# MiniD1_Schema.net
KiCad netlist of a schematic drawn in EAGLE
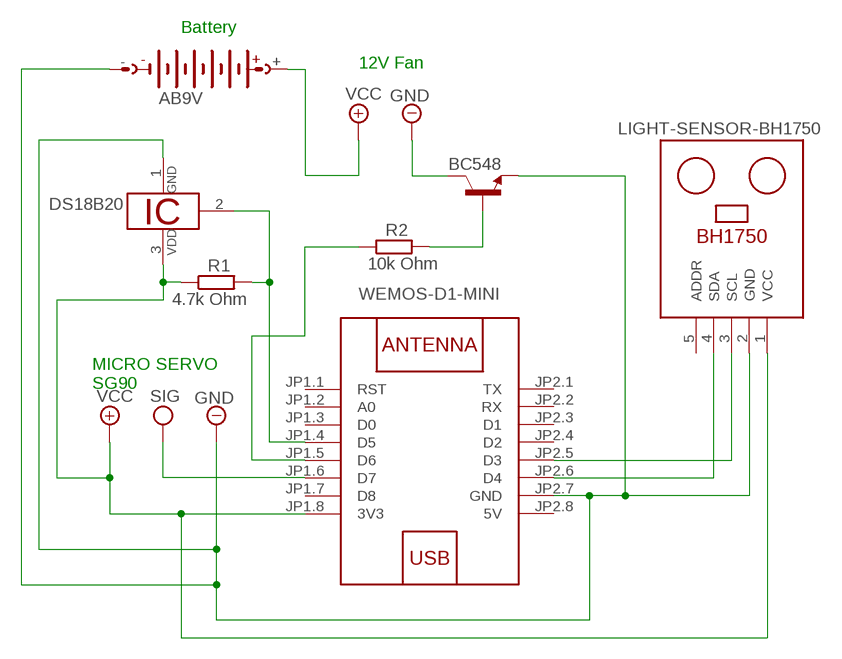
[diagram p0: schematic, sheet 1]

(export (version "E")
  (design (tool "Eeschema 10.0.6"))
  (components
    (comp (ref "G1")
      (value "AB9V")
      (footprint "eagle-import:AB9V")
      (libsource (lib "eagle-import") (part "AB9V"))
    )
    (comp (ref "IC1")
      (value "DS18B20")
      (footprint "eagle-import:TO92-")
      (libsource (lib "eagle-import") (part "DS18B20"))
    )
    (comp (ref "Q1")
      (value "BC548")
      (footprint "eagle-import:TO92-EBC")
      (libsource (lib "eagle-import") (part "BC548"))
    )
    (comp (ref "R1")
      (value "4.7k Ohm")
      (footprint "eagle-import:0207_10")
      (libsource (lib "eagle-import") (part "R-EU_0207/10"))
    )
    (comp (ref "R2")
      (value "10k Ohm")
      (footprint "eagle-import:0207_10")
      (libsource (lib "eagle-import") (part "R-EU_0207/10"))
    )
    (comp (ref "U$1")
      (value "WEMOS-D1-MINI")
      (footprint "eagle-import:WEMOS-D1-MINI")
      (libsource (lib "eagle-import") (part "WEMOS-D1-MINI"))
    )
    (comp (ref "U$2")
      (value "LIGHT-SENSOR-BH1750")
      (footprint "eagle-import:LIGHT-SENSOR-BH1750")
      (libsource (lib "eagle-import") (part "LIGHT-SENSOR-BH1750"))
    )
  )
  (nets
    (net (code "1") (name "/5V") (class "Default")
      (node (ref "U$1") (pin "JP2.8") (pinfunction "5V_JP2.8") (pintype "power_in"))
    )
    (net (code "2") (name "GND") (class "Default")
      (node (ref "G1") (pin "-") (pinfunction "-_-") (pintype "passive"))
      (node (ref "IC1") (pin "1") (pinfunction "GND_1") (pintype "power_in"))
      (node (ref "Q1") (pin "C") (pinfunction "C_C") (pintype "passive"))
      (node (ref "Q1") (pin "E") (pinfunction "E_E") (pintype "passive"))
      (node (ref "U$1") (pin "JP2.7") (pinfunction "GND_JP2.7") (pintype "power_in"))
      (node (ref "U$2") (pin "2") (pinfunction "GND_2") (pintype "power_in"))
    )
    (net (code "3") (name "Net-(IC1C-1W)") (class "Default")
      (node (ref "IC1") (pin "2") (pinfunction "1W_2") (pintype "power_in"))
      (node (ref "R1") (pin "2") (pinfunction "2_2") (pintype "passive"))
      (node (ref "U$1") (pin "JP1.4") (pinfunction "D5_JP1.4") (pintype "bidirectional"))
    )
    (net (code "4") (name "Net-(Q1-PadB)") (class "Default")
      (node (ref "Q1") (pin "B") (pinfunction "B_B") (pintype "passive"))
      (node (ref "R2") (pin "2") (pinfunction "2_2") (pintype "passive"))
    )
    (net (code "5") (name "Net-(U$1-D3)") (class "Default")
      (node (ref "U$1") (pin "JP2.5") (pinfunction "D3_JP2.5") (pintype "bidirectional"))
      (node (ref "U$2") (pin "3") (pinfunction "SCL_3") (pintype "bidirectional"))
    )
    (net (code "6") (name "Net-(U$1-D4)") (class "Default")
      (node (ref "U$1") (pin "JP2.6") (pinfunction "D4_JP2.6") (pintype "bidirectional"))
      (node (ref "U$2") (pin "4") (pinfunction "SDA_4") (pintype "bidirectional"))
    )
    (net (code "7") (name "Net-(U$1-D6)") (class "Default")
      (node (ref "R2") (pin "1") (pinfunction "1_1") (pintype "passive"))
      (node (ref "U$1") (pin "JP1.5") (pinfunction "D6_JP1.5") (pintype "bidirectional"))
    )
    (net (code "8") (name "SIG") (class "Default")
      (node (ref "U$1") (pin "JP1.6") (pinfunction "D7_JP1.6") (pintype "bidirectional"))
    )
    (net (code "9") (name "VCC") (class "Default")
      (node (ref "G1") (pin "+") (pinfunction "+_+") (pintype "passive"))
      (node (ref "IC1") (pin "3") (pinfunction "VDD_3") (pintype "power_in"))
      (node (ref "R1") (pin "1") (pinfunction "1_1") (pintype "passive"))
      (node (ref "U$1") (pin "JP1.8") (pinfunction "3V3_JP1.8") (pintype "power_in"))
      (node (ref "U$2") (pin "1") (pinfunction "VCC_1") (pintype "power_in"))
    )
    (net (code "10") (name "unconnected-(U$1-A0-PadJP1.2)") (class "Default")
      (node (ref "U$1") (pin "JP1.2") (pinfunction "A0_JP1.2") (pintype "bidirectional"))
    )
    (net (code "11") (name "unconnected-(U$1-D0-PadJP1.3)") (class "Default")
      (node (ref "U$1") (pin "JP1.3") (pinfunction "D0_JP1.3") (pintype "bidirectional"))
    )
    (net (code "12") (name "unconnected-(U$1-D1-PadJP2.3)") (class "Default")
      (node (ref "U$1") (pin "JP2.3") (pinfunction "D1_JP2.3") (pintype "bidirectional"))
    )
    (net (code "13") (name "unconnected-(U$1-D2-PadJP2.4)") (class "Default")
      (node (ref "U$1") (pin "JP2.4") (pinfunction "D2_JP2.4") (pintype "bidirectional"))
    )
    (net (code "14") (name "unconnected-(U$1-D8-PadJP1.7)") (class "Default")
      (node (ref "U$1") (pin "JP1.7") (pinfunction "D8_JP1.7") (pintype "bidirectional"))
    )
    (net (code "15") (name "unconnected-(U$1-RST-PadJP1.1)") (class "Default")
      (node (ref "U$1") (pin "JP1.1") (pinfunction "RST_JP1.1") (pintype "bidirectional"))
    )
    (net (code "16") (name "unconnected-(U$1-RX-PadJP2.2)") (class "Default")
      (node (ref "U$1") (pin "JP2.2") (pinfunction "RX_JP2.2") (pintype "bidirectional"))
    )
    (net (code "17") (name "unconnected-(U$1-TX-PadJP2.1)") (class "Default")
      (node (ref "U$1") (pin "JP2.1") (pinfunction "TX_JP2.1") (pintype "bidirectional"))
    )
    (net (code "18") (name "unconnected-(U$2-ADDR-Pad5)") (class "Default")
      (node (ref "U$2") (pin "5") (pinfunction "ADDR_5") (pintype "bidirectional"))
    )
  )
)
